# driver_V1_4.net
KiCad netlist of a schematic drawn in Altium Designer
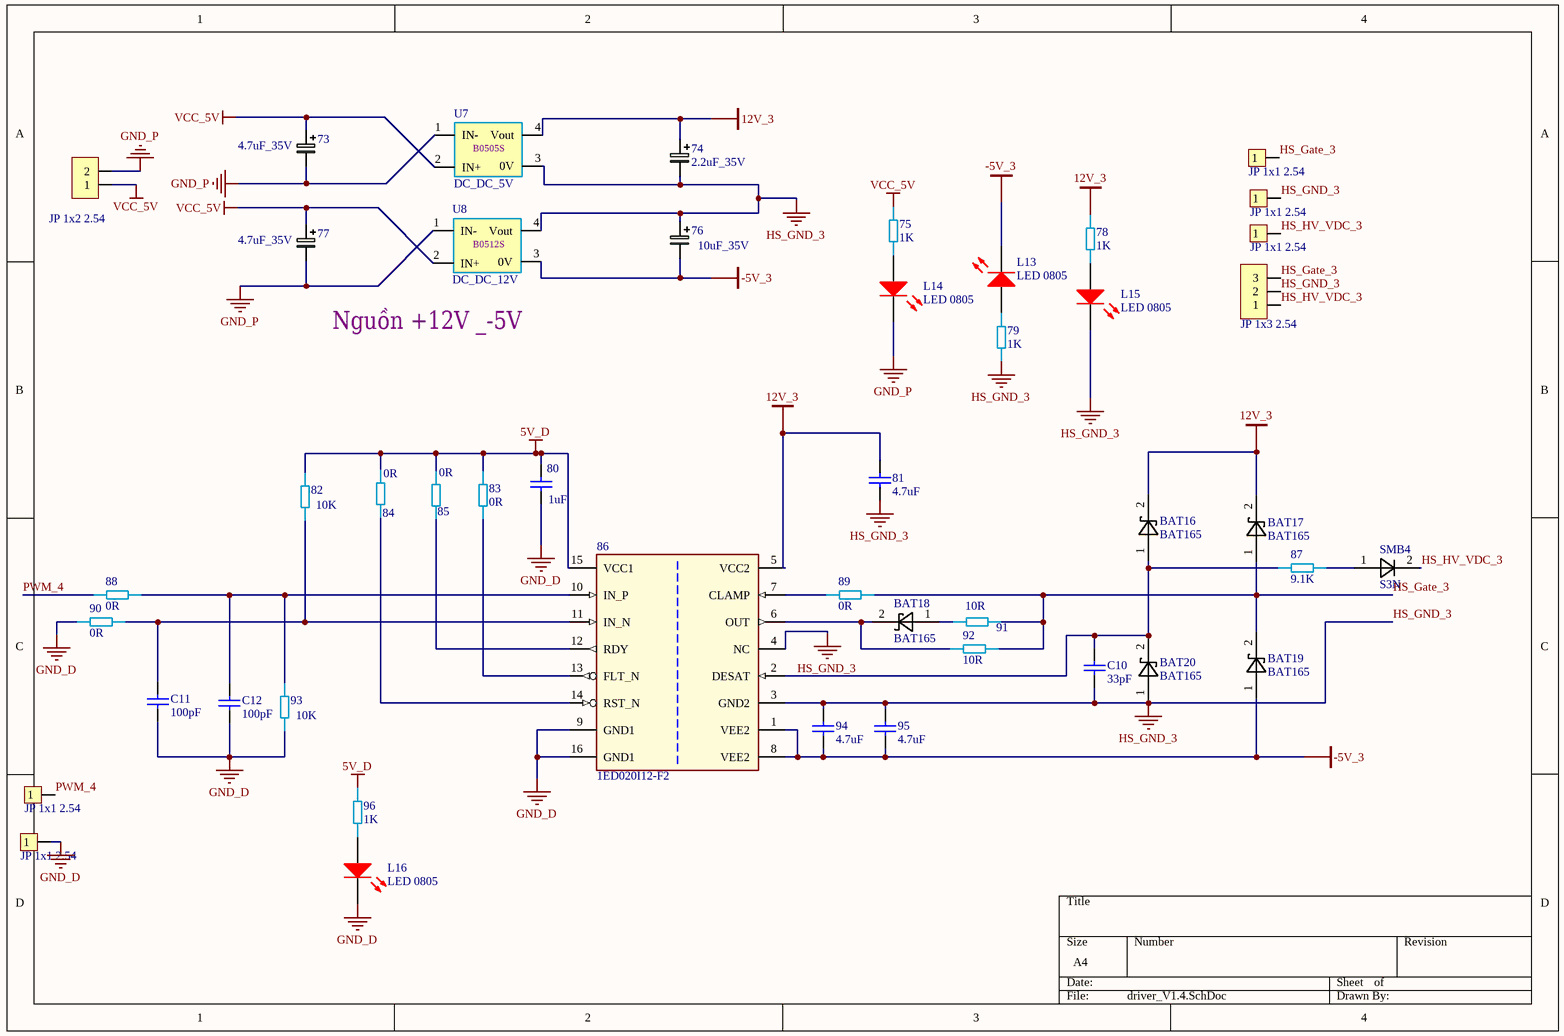
[diagram p0: driver_V1.4.SchDoc]

(export (version "E")
  (design (tool "Eeschema 10.0.6"))
  (components
    (comp (ref "73")
      (value "4.7uF_35V")
      (footprint "tu_4x5.4mm")
      (description "capacitor_electric")
      (libsource (lib "labari_altium1") (part "capacitor_electric"))
    )
    (comp (ref "74")
      (value "2.2uF_35V")
      (footprint "tu_4x5.4mm")
      (description "capacitor_electric")
      (libsource (lib "labari_altium1") (part "capacitor_electric"))
    )
    (comp (ref "75")
      (value "1K")
      (footprint "RES1206")
      (libsource (lib "labari_altium1") (part "311-0.0GRTR-ND"))
    )
    (comp (ref "76")
      (value "10uF_35V")
      (footprint "tu_4x5.4mm")
      (description "capacitor_electric")
      (libsource (lib "labari_altium1") (part "capacitor_electric"))
    )
    (comp (ref "77")
      (value "4.7uF_35V")
      (footprint "tu_4x5.4mm")
      (description "capacitor_electric")
      (libsource (lib "labari_altium1") (part "capacitor_electric"))
    )
    (comp (ref "78")
      (value "1K")
      (footprint "RES1206")
      (libsource (lib "labari_altium1") (part "311-0.0GRTR-ND"))
    )
    (comp (ref "79")
      (value "1K")
      (footprint "RES1206")
      (libsource (lib "labari_altium1") (part "311-0.0GRTR-ND"))
    )
    (comp (ref "80")
      (value "1uF")
      (footprint "Tu 0805_N")
      (libsource (lib "labari_altium1") (part "cap_0805"))
    )
    (comp (ref "81")
      (value "4.7uF")
      (footprint "tu 1206_N")
      (libsource (lib "labari_altium1") (part "cap_1210"))
    )
    (comp (ref "82")
      (value "10K")
      (footprint "RES1206")
      (libsource (lib "labari_altium1") (part "311-0.0GRTR-ND"))
    )
    (comp (ref "83")
      (value "0R")
      (footprint "RES1206")
      (libsource (lib "labari_altium1") (part "311-0.0GRTR-ND"))
    )
    (comp (ref "84")
      (value "0R")
      (footprint "RES1206")
      (libsource (lib "labari_altium1") (part "311-0.0GRTR-ND"))
    )
    (comp (ref "85")
      (value "0R")
      (footprint "RES1206")
      (libsource (lib "labari_altium1") (part "311-0.0GRTR-ND"))
    )
    (comp (ref "86")
      (value "1ED020I12-F2")
      (footprint "SOIC127P1028X264-16N-1")
      (description "Single IGBT Driver IC")
      (fields (field (name "MANUFACTURER") "Infineon Technologies"))
      (libsource (lib "labari_altium1") (part "1ED020I12-F2"))
    )
    (comp (ref "87")
      (value "9.1K")
      (footprint "RES_2512")
      (libsource (lib "labari_altium1") (part "311-0.0GRTR-ND"))
    )
    (comp (ref "88")
      (value "0R")
      (footprint "RES1206")
      (libsource (lib "labari_altium1") (part "311-0.0GRTR-ND"))
    )
    (comp (ref "89")
      (value "0R")
      (footprint "RES_2512")
      (libsource (lib "labari_altium1") (part "311-0.0GRTR-ND"))
    )
    (comp (ref "90")
      (value "0R")
      (footprint "RES1206")
      (libsource (lib "labari_altium1") (part "311-0.0GRTR-ND"))
    )
    (comp (ref "91")
      (value "10R")
      (footprint "RES_2512")
      (libsource (lib "labari_altium1") (part "311-0.0GRTR-ND"))
    )
    (comp (ref "92")
      (value "10R")
      (footprint "RES_2512")
      (libsource (lib "labari_altium1") (part "311-0.0GRTR-ND"))
    )
    (comp (ref "93")
      (value "10K")
      (footprint "RES1206")
      (libsource (lib "labari_altium1") (part "311-0.0GRTR-ND"))
    )
    (comp (ref "94")
      (value "4.7uF")
      (footprint "tu 1206_N")
      (libsource (lib "labari_altium1") (part "cap_1210"))
    )
    (comp (ref "95")
      (value "4.7uF")
      (footprint "tu 1206_N")
      (libsource (lib "labari_altium1") (part "cap_1210"))
    )
    (comp (ref "96")
      (value "1K")
      (footprint "RES1206")
      (libsource (lib "labari_altium1") (part "311-0.0GRTR-ND"))
    )
    (comp (ref "BAT16") (value "BAT165") (footprint "SMB") (libsource (lib "labari_altium1") (part "BAT165")))
    (comp (ref "BAT17") (value "BAT165") (footprint "SMB") (libsource (lib "labari_altium1") (part "BAT165")))
    (comp (ref "BAT18") (value "BAT165") (footprint "SMB") (libsource (lib "labari_altium1") (part "BAT165")))
    (comp (ref "BAT19") (value "BAT165") (footprint "SMB") (libsource (lib "labari_altium1") (part "BAT165")))
    (comp (ref "BAT20") (value "BAT165") (footprint "SMB") (libsource (lib "labari_altium1") (part "BAT165")))
    (comp (ref "C10")
      (value "33pF")
      (footprint "Tu 0805_N")
      (libsource (lib "labari_altium1") (part "cap_0805"))
    )
    (comp (ref "C11")
      (value "100pF")
      (footprint "Tu 0805_N")
      (libsource (lib "labari_altium1") (part "cap_0805"))
    )
    (comp (ref "C12")
      (value "100pF")
      (footprint "Tu 0805_N")
      (libsource (lib "labari_altium1") (part "cap_0805"))
    )
    (comp (ref "JP23")
      (value "JP 1x1 2.54")
      (footprint "test_point")
      (description "Cắm")
      (libsource (lib "labari_altium1") (part "JP 1x1 2.54 Duc Thang"))
    )
    (comp (ref "JP24")
      (value "JP 1x2 2.54")
      (footprint "JP 1x2 DT_n")
      (description "Cắm")
      (libsource (lib "labari_altium1") (part "JP 1x2 2.54 Duc Thang"))
    )
    (comp (ref "JP25")
      (value "JP 1x1 2.54")
      (footprint "test_point")
      (description "Cắm")
      (libsource (lib "labari_altium1") (part "JP 1x1 2.54 Duc Thang"))
    )
    (comp (ref "JP26")
      (value "JP 1x1 2.54")
      (footprint "test_point")
      (description "Cắm")
      (libsource (lib "labari_altium1") (part "JP 1x1 2.54 Duc Thang"))
    )
    (comp (ref "JP27")
      (value "JP 1x3 2.54")
      (footprint "XH2.54M-3")
      (description "Cắm")
      (libsource (lib "labari_altium1") (part "JP 1x3 2.54 Duc Cong"))
    )
    (comp (ref "JP28")
      (value "JP 1x1 2.54")
      (footprint "test_point")
      (description "Cắm")
      (libsource (lib "labari_altium1") (part "JP 1x1 2.54 Duc Thang"))
    )
    (comp (ref "JP29")
      (value "JP 1x1 2.54")
      (footprint "test_point")
      (description "Cắm")
      (libsource (lib "labari_altium1") (part "JP 1x1 2.54 Duc Thang"))
    )
    (comp (ref "L13")
      (value "LED 0805")
      (footprint "LED-0805-Red")
      (description "Dán")
      (libsource (lib "labari_altium1") (part "LED 0805 Do"))
    )
    (comp (ref "L14")
      (value "LED 0805")
      (footprint "LED-0805-Red")
      (description "Dán")
      (libsource (lib "labari_altium1") (part "LED 0805 Do"))
    )
    (comp (ref "L15")
      (value "LED 0805")
      (footprint "LED-0805-Red")
      (description "Dán")
      (libsource (lib "labari_altium1") (part "LED 0805 Do"))
    )
    (comp (ref "L16")
      (value "LED 0805")
      (footprint "LED-0805-Red")
      (description "Dán")
      (libsource (lib "labari_altium1") (part "LED 0805 Do"))
    )
    (comp (ref "SMB4") (value "S3N") (footprint "SMB") (libsource (lib "labari_altium1") (part "S3A-S3N")))
    (comp (ref "U7")
      (value "DC_DC_5V")
      (footprint "B0505S/D-1W")
      (libsource (lib "labari_altium1") (part "DC_DC_5v"))
    )
    (comp (ref "U8")
      (value "DC_DC_12V")
      (footprint "B0512S/D-1W")
      (libsource (lib "labari_altium1") (part "DC_DC_12v"))
    )
  )
  (nets
    (net (code "1") (name "-5V_3") (class "Default")
      (node (ref "76") (pin "2") (pinfunction "2_2") (pintype "passive"))
      (node (ref "86") (pin "1") (pinfunction "VEE2_1") (pintype "power_in"))
      (node (ref "86") (pin "8") (pinfunction "VEE2_8") (pintype "power_in"))
      (node (ref "94") (pin "1") (pinfunction "1_1") (pintype "passive"))
      (node (ref "95") (pin "1") (pinfunction "1_1") (pintype "passive"))
      (node (ref "BAT19") (pin "1") (pinfunction "1_1") (pintype "passive"))
      (node (ref "L13") (pin "2") (pinfunction "K_2") (pintype "passive"))
      (node (ref "U8") (pin "3") (pinfunction "0V_3") (pintype "passive"))
    )
    (net (code "2") (name "/HS_Gate_3") (class "Default")
      (node (ref "89") (pin "2") (pinfunction "2_2") (pintype "passive"))
      (node (ref "91") (pin "2") (pinfunction "2_2") (pintype "passive"))
      (node (ref "92") (pin "2") (pinfunction "2_2") (pintype "passive"))
      (node (ref "BAT17") (pin "1") (pinfunction "1_1") (pintype "passive"))
      (node (ref "BAT19") (pin "2") (pinfunction "2_2") (pintype "passive"))
      (node (ref "JP23") (pin "1") (pinfunction "1_1") (pintype "passive"))
      (node (ref "JP27") (pin "3") (pinfunction "3_3") (pintype "passive"))
    )
    (net (code "3") (name "/HS_HV_VDC_3") (class "Default")
      (node (ref "JP26") (pin "1") (pinfunction "1_1") (pintype "passive"))
      (node (ref "JP27") (pin "1") (pinfunction "1_1") (pintype "passive"))
      (node (ref "SMB4") (pin "2") (pinfunction "2_2") (pintype "passive"))
    )
    (net (code "4") (name "/PWM_4") (class "Default")
      (node (ref "88") (pin "2") (pinfunction "2_2") (pintype "passive"))
      (node (ref "JP28") (pin "1") (pinfunction "1_1") (pintype "passive"))
    )
    (net (code "5") (name "5V_D") (class "Default")
      (node (ref "80") (pin "2") (pinfunction "2_2") (pintype "passive"))
      (node (ref "82") (pin "2") (pinfunction "2_2") (pintype "passive"))
      (node (ref "83") (pin "1") (pinfunction "1_1") (pintype "passive"))
      (node (ref "84") (pin "2") (pinfunction "2_2") (pintype "passive"))
      (node (ref "85") (pin "1") (pinfunction "1_1") (pintype "passive"))
      (node (ref "86") (pin "15") (pinfunction "VCC1_15") (pintype "power_in"))
      (node (ref "96") (pin "1") (pinfunction "1_1") (pintype "passive"))
    )
    (net (code "6") (name "12V_3") (class "Default")
      (node (ref "74") (pin "1") (pinfunction "1_1") (pintype "passive"))
      (node (ref "78") (pin "1") (pinfunction "1_1") (pintype "passive"))
      (node (ref "81") (pin "2") (pinfunction "2_2") (pintype "passive"))
      (node (ref "86") (pin "5") (pinfunction "VCC2_5") (pintype "power_in"))
      (node (ref "BAT16") (pin "2") (pinfunction "2_2") (pintype "passive"))
      (node (ref "BAT17") (pin "2") (pinfunction "2_2") (pintype "passive"))
      (node (ref "U7") (pin "4") (pinfunction "Vout_4") (pintype "passive"))
    )
    (net (code "7") (name "GND_D") (class "Default")
      (node (ref "80") (pin "1") (pinfunction "1_1") (pintype "passive"))
      (node (ref "86") (pin "16") (pinfunction "GND1_16") (pintype "power_in"))
      (node (ref "86") (pin "9") (pinfunction "GND1_9") (pintype "power_in"))
      (node (ref "90") (pin "2") (pinfunction "2_2") (pintype "passive"))
      (node (ref "93") (pin "1") (pinfunction "1_1") (pintype "passive"))
      (node (ref "C11") (pin "1") (pinfunction "1_1") (pintype "passive"))
      (node (ref "C12") (pin "1") (pinfunction "1_1") (pintype "passive"))
      (node (ref "JP29") (pin "1") (pinfunction "1_1") (pintype "passive"))
      (node (ref "L16") (pin "2") (pinfunction "K_2") (pintype "passive"))
    )
    (net (code "8") (name "GND_P") (class "Default")
      (node (ref "73") (pin "2") (pinfunction "2_2") (pintype "passive"))
      (node (ref "77") (pin "2") (pinfunction "2_2") (pintype "passive"))
      (node (ref "JP24") (pin "2") (pinfunction "2_2") (pintype "passive"))
      (node (ref "L14") (pin "2") (pinfunction "K_2") (pintype "passive"))
      (node (ref "U7") (pin "1") (pinfunction "IN-_1") (pintype "passive"))
      (node (ref "U8") (pin "1") (pinfunction "IN-_1") (pintype "passive"))
    )
    (net (code "9") (name "HS_GND_3") (class "Default")
      (node (ref "74") (pin "2") (pinfunction "2_2") (pintype "passive"))
      (node (ref "76") (pin "1") (pinfunction "1_1") (pintype "passive"))
      (node (ref "79") (pin "2") (pinfunction "2_2") (pintype "passive"))
      (node (ref "81") (pin "1") (pinfunction "1_1") (pintype "passive"))
      (node (ref "86") (pin "3") (pinfunction "GND2_3") (pintype "power_in"))
      (node (ref "86") (pin "4") (pinfunction "NC_4") (pintype "passive"))
      (node (ref "94") (pin "2") (pinfunction "2_2") (pintype "passive"))
      (node (ref "95") (pin "2") (pinfunction "2_2") (pintype "passive"))
      (node (ref "BAT20") (pin "1") (pinfunction "1_1") (pintype "passive"))
      (node (ref "C10") (pin "1") (pinfunction "1_1") (pintype "passive"))
      (node (ref "JP25") (pin "1") (pinfunction "1_1") (pintype "passive"))
      (node (ref "JP27") (pin "2") (pinfunction "2_2") (pintype "passive"))
      (node (ref "L15") (pin "2") (pinfunction "K_2") (pintype "passive"))
      (node (ref "U7") (pin "3") (pinfunction "0V_3") (pintype "passive"))
      (node (ref "U8") (pin "4") (pinfunction "Vout_4") (pintype "passive"))
    )
    (net (code "10") (name "Net-(86-CLAMP)") (class "Default")
      (node (ref "86") (pin "7") (pinfunction "CLAMP_7") (pintype "input"))
      (node (ref "89") (pin "1") (pinfunction "1_1") (pintype "passive"))
    )
    (net (code "11") (name "Net-(86-DESAT)") (class "Default")
      (node (ref "86") (pin "2") (pinfunction "DESAT_2") (pintype "input"))
      (node (ref "87") (pin "1") (pinfunction "1_1") (pintype "passive"))
      (node (ref "BAT16") (pin "1") (pinfunction "1_1") (pintype "passive"))
      (node (ref "BAT20") (pin "2") (pinfunction "2_2") (pintype "passive"))
      (node (ref "C10") (pin "2") (pinfunction "2_2") (pintype "passive"))
    )
    (net (code "12") (name "Net-(86-FLT_N)") (class "Default")
      (node (ref "83") (pin "2") (pinfunction "2_2") (pintype "passive"))
      (node (ref "86") (pin "13") (pinfunction "FLT_N_13") (pintype "output"))
    )
    (net (code "13") (name "Net-(86-IN_N)") (class "Default")
      (node (ref "82") (pin "1") (pinfunction "1_1") (pintype "passive"))
      (node (ref "86") (pin "11") (pinfunction "IN_N_11") (pintype "input"))
      (node (ref "90") (pin "1") (pinfunction "1_1") (pintype "passive"))
      (node (ref "C11") (pin "2") (pinfunction "2_2") (pintype "passive"))
    )
    (net (code "14") (name "Net-(86-IN_P)") (class "Default")
      (node (ref "86") (pin "10") (pinfunction "IN_P_10") (pintype "input"))
      (node (ref "88") (pin "1") (pinfunction "1_1") (pintype "passive"))
      (node (ref "93") (pin "2") (pinfunction "2_2") (pintype "passive"))
      (node (ref "C12") (pin "2") (pinfunction "2_2") (pintype "passive"))
    )
    (net (code "15") (name "Net-(86-OUT)") (class "Default")
      (node (ref "86") (pin "6") (pinfunction "OUT_6") (pintype "output"))
      (node (ref "92") (pin "1") (pinfunction "1_1") (pintype "passive"))
      (node (ref "BAT18") (pin "2") (pinfunction "2_2") (pintype "passive"))
    )
    (net (code "16") (name "Net-(86-RDY)") (class "Default")
      (node (ref "85") (pin "2") (pinfunction "2_2") (pintype "passive"))
      (node (ref "86") (pin "12") (pinfunction "RDY_12") (pintype "output"))
    )
    (net (code "17") (name "Net-(86-RST_N)") (class "Default")
      (node (ref "84") (pin "1") (pinfunction "1_1") (pintype "passive"))
      (node (ref "86") (pin "14") (pinfunction "RST_N_14") (pintype "input"))
    )
    (net (code "18") (name "Net-(87-Pad2)") (class "Default")
      (node (ref "87") (pin "2") (pinfunction "2_2") (pintype "passive"))
      (node (ref "SMB4") (pin "1") (pinfunction "1_1") (pintype "passive"))
    )
    (net (code "19") (name "Net-(91-Pad1)") (class "Default")
      (node (ref "91") (pin "1") (pinfunction "1_1") (pintype "passive"))
      (node (ref "BAT18") (pin "1") (pinfunction "1_1") (pintype "passive"))
    )
    (net (code "20") (name "Net-(L13-A)") (class "Default")
      (node (ref "79") (pin "1") (pinfunction "1_1") (pintype "passive"))
      (node (ref "L13") (pin "1") (pinfunction "A_1") (pintype "passive"))
    )
    (net (code "21") (name "Net-(L14-A)") (class "Default")
      (node (ref "75") (pin "2") (pinfunction "2_2") (pintype "passive"))
      (node (ref "L14") (pin "1") (pinfunction "A_1") (pintype "passive"))
    )
    (net (code "22") (name "Net-(L15-A)") (class "Default")
      (node (ref "78") (pin "2") (pinfunction "2_2") (pintype "passive"))
      (node (ref "L15") (pin "1") (pinfunction "A_1") (pintype "passive"))
    )
    (net (code "23") (name "Net-(L16-A)") (class "Default")
      (node (ref "96") (pin "2") (pinfunction "2_2") (pintype "passive"))
      (node (ref "L16") (pin "1") (pinfunction "A_1") (pintype "passive"))
    )
    (net (code "24") (name "VCC_5V") (class "Default")
      (node (ref "73") (pin "1") (pinfunction "1_1") (pintype "passive"))
      (node (ref "75") (pin "1") (pinfunction "1_1") (pintype "passive"))
      (node (ref "77") (pin "1") (pinfunction "1_1") (pintype "passive"))
      (node (ref "JP24") (pin "1") (pinfunction "1_1") (pintype "passive"))
      (node (ref "U7") (pin "2") (pinfunction "IN+_2") (pintype "passive"))
      (node (ref "U8") (pin "2") (pinfunction "IN+_2") (pintype "passive"))
    )
  )
)
